# Sheet1.net
KiCad netlist of a schematic drawn in Altium Designer
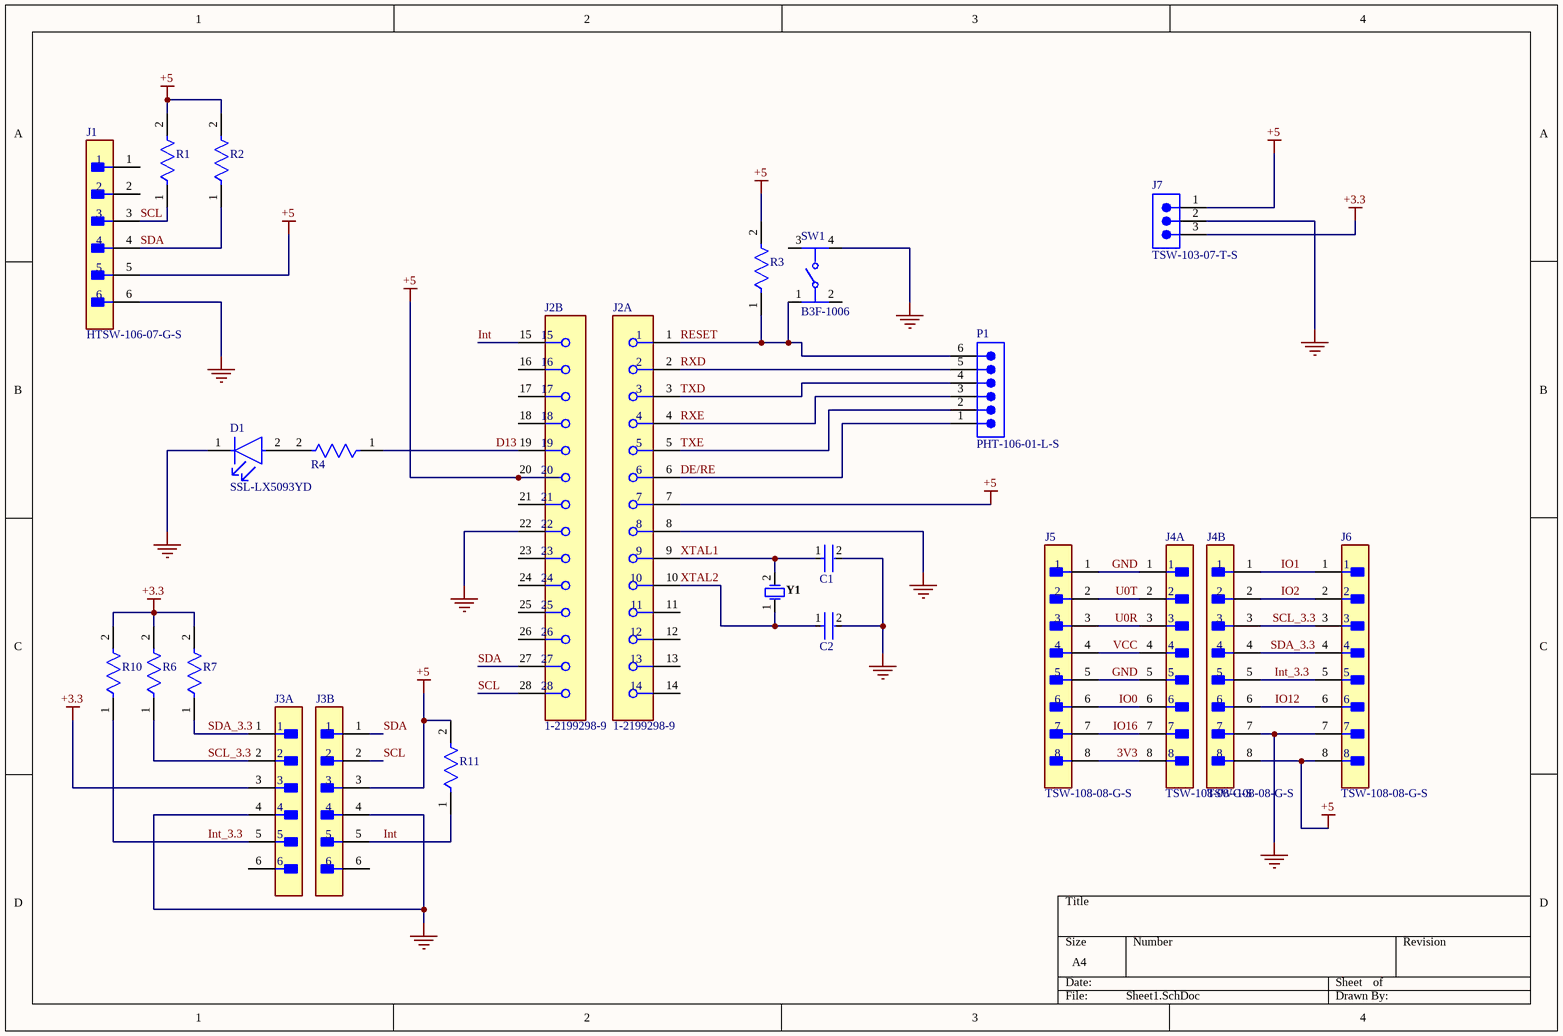
[diagram p0: Sheet1.SchDoc]

(export (version "E")
  (design (tool "Eeschema 10.0.6"))
  (components
    (comp (ref "C1")
      (value "RCE5C1H220J0DBH03A")
      (footprint "FP-RCE0DB-MFG")
      (description "Cap Ceramic 22pF 50V C0G ±5% Radial 2.5mm +125°C Ammo Pack")
      (fields (field (name "TOLERANCE") "5%"))
      (libsource (lib "Altium Content Vault") (part "b4654b650e69147ec39a6b967a45e02"))
    )
    (comp (ref "C2")
      (value "RCE5C1H220J0DBH03A")
      (footprint "FP-RCE0DB-MFG")
      (description "Cap Ceramic 22pF 50V C0G ±5% Radial 2.5mm +125°C Ammo Pack")
      (fields (field (name "TOLERANCE") "5%"))
      (libsource (lib "Altium Content Vault") (part "b4654b650e69147ec39a6b967a45e02"))
    )
    (comp (ref "D1")
      (value "SSL-LX5093YD")
      (footprint "FP-SSL-LX5093YD-MFG")
      (description "LED YELLOW DIFFUSED T-1 3/4 T/H")
      (libsource (lib "Altium Content Vault") (part "8706943c75ba83719d021d2fdc84c58"))
    )
    (comp (ref "J1")
      (value "HTSW-106-07-G-S")
      (footprint "FP-HTSW-106-07-G-S-MFG")
      (description "CONN HEADER VERT 6POS 2.54MM")
      (libsource (lib "Altium Content Vault") (part "f2cb566baf1c37ab5a3b8e90bbeafd6"))
    )
    (comp (ref "J2")
      (value "1-2199298-9")
      (footprint "FP-1-2199298-9-MFG")
      (description "CONN IC DIP SOCKET 28POS TIN")
      (libsource (lib "") (part "9ff29dcfa3a67afbf451aa7ba5e588e_1"))
    )
    (comp (ref "J3A")
      (value "TSW-106-22-G-S")
      (footprint "FP-TSW-106-22-G-S-MFG")
      (description "CONN HEADER VERT 6POS 2.54MM")
      (libsource (lib "") (part "11692be1245668b174829cb8722fdf5_1"))
    )
    (comp (ref "J3B")
      (value "TSW-106-22-G-S")
      (footprint "FP-TSW-106-22-G-S-MFG")
      (description "CONN HEADER VERT 6POS 2.54MM")
      (libsource (lib "Altium Content Vault") (part "11692be1245668b174829cb8722fdf5"))
    )
    (comp (ref "J4A")
      (value "TSW-108-08-G-S")
      (footprint "FP-TSW-108-08-G-S-MFG")
      (description "CONN HEADER VERT 8POS 2.54MM")
      (fields
        (field (name "MANUFACTURER") "Samtec")
        (field (name "OCTOPART") "https://octopart.com/tsw-108-08-g-s-samtec-272653")
      )
      (libsource (lib "") (part "99ec2b232beb5d2356d4d77f6a047f0_1"))
    )
    (comp (ref "J4B")
      (value "TSW-108-08-G-S")
      (footprint "FP-TSW-108-08-G-S-MFG")
      (description "CONN HEADER VERT 8POS 2.54MM")
      (fields
        (field (name "MANUFACTURER") "Samtec")
        (field (name "OCTOPART") "https://octopart.com/tsw-108-08-g-s-samtec-272653")
      )
      (libsource (lib "Altium Content Vault") (part "99ec2b232beb5d2356d4d77f6a047f0"))
    )
    (comp (ref "J5")
      (value "TSW-108-08-G-S")
      (footprint "FP-TSW-108-08-G-S-MFG")
      (description "CONN HEADER VERT 8POS 2.54MM")
      (fields
        (field (name "MANUFACTURER") "Samtec")
        (field (name "OCTOPART") "https://octopart.com/tsw-108-08-g-s-samtec-272653")
      )
      (libsource (lib "Altium Content Vault") (part "99ec2b232beb5d2356d4d77f6a047f0"))
    )
    (comp (ref "J6")
      (value "TSW-108-08-G-S")
      (footprint "FP-TSW-108-08-G-S-MFG")
      (description "CONN HEADER VERT 8POS 2.54MM")
      (fields
        (field (name "MANUFACTURER") "Samtec")
        (field (name "OCTOPART") "https://octopart.com/tsw-108-08-g-s-samtec-272653")
      )
      (libsource (lib "") (part "99ec2b232beb5d2356d4d77f6a047f0_1"))
    )
    (comp (ref "J7")
      (value "TSW-103-07-T-S")
      (footprint "SMTC-TSW-103-07-X-S")
      (description "0.025\" SQ Post Header, Through-hole, Vertical, -55 to 105 degC, 2.54 mm Pitch, 3-Pin, Male, RoHS")
      (fields (field (name "MANUFACTURER") "Samtec"))
      (libsource (lib "Altium Content Vault") (part "SMTC-TSW-103-X-X-S-X"))
    )
    (comp (ref "P1")
      (value "PHT-106-01-L-S")
      (footprint "SMTC-PHT-106-01-X-S")
      (description "Press Fit Header, Through-hole, Vertical, -55 to 125 degC, 2.54 mm Pitch, 6-Pin, Male, RoHS")
      (fields (field (name "MANUFACTURER") "Samtec"))
      (libsource (lib "Altium Content Vault") (part "SMTC-PHT-106-01-X-S"))
    )
    (comp (ref "R1")
      (value "VR37000001204JA100")
      (footprint "FP-VR37-MFG")
      (description "RES 1.2M OHM 5% 1/2W AXIAL")
      (fields (field (name "TOLERANCE") "5%"))
      (libsource (lib "Altium Content Vault") (part "1029c3af85768c4190bb7ad29bc67b5"))
    )
    (comp (ref "R2")
      (value "VR37000001204JA100")
      (footprint "FP-VR37-MFG")
      (description "RES 1.2M OHM 5% 1/2W AXIAL")
      (fields (field (name "TOLERANCE") "5%"))
      (libsource (lib "Altium Content Vault") (part "1029c3af85768c4190bb7ad29bc67b5"))
    )
    (comp (ref "R3")
      (value "VR37000001204JA100")
      (footprint "FP-VR37-MFG")
      (description "RES 1.2M OHM 5% 1/2W AXIAL")
      (fields (field (name "TOLERANCE") "5%"))
      (libsource (lib "Altium Content Vault") (part "1029c3af85768c4190bb7ad29bc67b5"))
    )
    (comp (ref "R4")
      (value "VR37000001204JA100")
      (footprint "FP-VR37-MFG")
      (description "RES 1.2M OHM 5% 1/2W AXIAL")
      (fields (field (name "TOLERANCE") "5%"))
      (libsource (lib "Altium Content Vault") (part "1029c3af85768c4190bb7ad29bc67b5"))
    )
    (comp (ref "R6")
      (value "VR37000001204JA100")
      (footprint "FP-VR37-MFG")
      (description "RES 1.2M OHM 5% 1/2W AXIAL")
      (fields (field (name "TOLERANCE") "5%"))
      (libsource (lib "Altium Content Vault") (part "1029c3af85768c4190bb7ad29bc67b5"))
    )
    (comp (ref "R7")
      (value "VR37000001204JA100")
      (footprint "FP-VR37-MFG")
      (description "RES 1.2M OHM 5% 1/2W AXIAL")
      (fields (field (name "TOLERANCE") "5%"))
      (libsource (lib "Altium Content Vault") (part "1029c3af85768c4190bb7ad29bc67b5"))
    )
    (comp (ref "R10")
      (value "VR37000001204JA100")
      (footprint "FP-VR37-MFG")
      (description "RES 1.2M OHM 5% 1/2W AXIAL")
      (fields (field (name "TOLERANCE") "5%"))
      (libsource (lib "Altium Content Vault") (part "1029c3af85768c4190bb7ad29bc67b5"))
    )
    (comp (ref "R11")
      (value "VR37000001204JA100")
      (footprint "FP-VR37-MFG")
      (description "RES 1.2M OHM 5% 1/2W AXIAL")
      (fields (field (name "TOLERANCE") "5%"))
      (libsource (lib "Altium Content Vault") (part "1029c3af85768c4190bb7ad29bc67b5"))
    )
    (comp (ref "SW1")
      (value "B3F-1006")
      (footprint "FP-B3F-1006-MFG")
      (description "SWITCH TACTILE SPST-NO 0.05A 24V")
      (libsource (lib "Altium Content Vault") (part "b8895f3f4cefb76e1819d2863dba89b"))
    )
    (comp (ref "Y1")
      (value "FOXSLF/160-20")
      (footprint "FOX-FOXSLF160-20")
      (description "Resistance Weld Thru-Hole Crystal, 16 MHz, -20 to 70 degC, 2-Pin THD, RoHS, Bulk")
      (fields (field (name "TOLERANCE") "1%"))
      (libsource (lib "Altium Content Vault") (part "XTAL-1-2-2"))
    )
  )
  (nets
    (net (code "1") (name "+3.3") (class "Default")
      (node (ref "J3A") (pin "3") (pinfunction "3_3") (pintype "passive"))
      (node (ref "J7") (pin "3") (pinfunction "3_3") (pintype "passive"))
      (node (ref "R10") (pin "2") (pinfunction "2_2") (pintype "passive"))
      (node (ref "R6") (pin "2") (pinfunction "2_2") (pintype "passive"))
      (node (ref "R7") (pin "2") (pinfunction "2_2") (pintype "passive"))
    )
    (net (code "2") (name "+5") (class "Default")
      (node (ref "J1") (pin "5") (pinfunction "5_5") (pintype "passive"))
      (node (ref "J2") (pin "20") (pinfunction "20_20") (pintype "passive"))
      (node (ref "J2") (pin "7") (pinfunction "7_7") (pintype "passive"))
      (node (ref "J3B") (pin "3") (pinfunction "3_3") (pintype "passive"))
      (node (ref "J4B") (pin "8") (pinfunction "8_8") (pintype "passive"))
      (node (ref "J6") (pin "8") (pinfunction "8_8") (pintype "passive"))
      (node (ref "J7") (pin "1") (pinfunction "1_1") (pintype "passive"))
      (node (ref "R1") (pin "2") (pinfunction "2_2") (pintype "passive"))
      (node (ref "R11") (pin "2") (pinfunction "2_2") (pintype "passive"))
      (node (ref "R2") (pin "2") (pinfunction "2_2") (pintype "passive"))
      (node (ref "R3") (pin "2") (pinfunction "2_2") (pintype "passive"))
    )
    (net (code "3") (name "/3V3") (class "Default")
      (node (ref "J4A") (pin "8") (pinfunction "8_8") (pintype "passive"))
      (node (ref "J5") (pin "8") (pinfunction "8_8") (pintype "passive"))
    )
    (net (code "4") (name "/D13") (class "Default")
      (node (ref "J2") (pin "19") (pinfunction "19_19") (pintype "passive"))
      (node (ref "R4") (pin "1") (pinfunction "1_1") (pintype "passive"))
    )
    (net (code "5") (name "/DE{slash}RE") (class "Default")
      (node (ref "J2") (pin "6") (pinfunction "6_6") (pintype "passive"))
      (node (ref "P1") (pin "1") (pinfunction "1_1") (pintype "passive"))
    )
    (net (code "6") (name "/IO0") (class "Default")
      (node (ref "J4A") (pin "6") (pinfunction "6_6") (pintype "passive"))
      (node (ref "J5") (pin "6") (pinfunction "6_6") (pintype "passive"))
    )
    (net (code "7") (name "/IO1") (class "Default")
      (node (ref "J4B") (pin "1") (pinfunction "1_1") (pintype "passive"))
      (node (ref "J6") (pin "1") (pinfunction "1_1") (pintype "passive"))
    )
    (net (code "8") (name "/IO2") (class "Default")
      (node (ref "J4B") (pin "2") (pinfunction "2_2") (pintype "passive"))
      (node (ref "J6") (pin "2") (pinfunction "2_2") (pintype "passive"))
    )
    (net (code "9") (name "/IO12") (class "Default")
      (node (ref "J4B") (pin "6") (pinfunction "6_6") (pintype "passive"))
      (node (ref "J6") (pin "6") (pinfunction "6_6") (pintype "passive"))
    )
    (net (code "10") (name "/IO16") (class "Default")
      (node (ref "J4A") (pin "7") (pinfunction "7_7") (pintype "passive"))
      (node (ref "J5") (pin "7") (pinfunction "7_7") (pintype "passive"))
    )
    (net (code "11") (name "/Int") (class "Default")
      (node (ref "J2") (pin "15") (pinfunction "15_15") (pintype "passive"))
      (node (ref "J3B") (pin "5") (pinfunction "5_5") (pintype "passive"))
      (node (ref "R11") (pin "1") (pinfunction "1_1") (pintype "passive"))
    )
    (net (code "12") (name "/Int_3.3") (class "Default")
      (node (ref "J3A") (pin "5") (pinfunction "5_5") (pintype "passive"))
      (node (ref "J4B") (pin "5") (pinfunction "5_5") (pintype "passive"))
      (node (ref "J6") (pin "5") (pinfunction "5_5") (pintype "passive"))
      (node (ref "R10") (pin "1") (pinfunction "1_1") (pintype "passive"))
    )
    (net (code "13") (name "/RESET") (class "Default")
      (node (ref "J2") (pin "1") (pinfunction "1_1") (pintype "passive"))
      (node (ref "P1") (pin "6") (pinfunction "6_6") (pintype "passive"))
      (node (ref "R3") (pin "1") (pinfunction "1_1") (pintype "passive"))
      (node (ref "SW1") (pin "1") (pinfunction "1_1") (pintype "passive"))
    )
    (net (code "14") (name "/RXD") (class "Default")
      (node (ref "J2") (pin "2") (pinfunction "2_2") (pintype "passive"))
      (node (ref "P1") (pin "5") (pinfunction "5_5") (pintype "passive"))
    )
    (net (code "15") (name "/RXE") (class "Default")
      (node (ref "J2") (pin "4") (pinfunction "4_4") (pintype "passive"))
      (node (ref "P1") (pin "3") (pinfunction "3_3") (pintype "passive"))
    )
    (net (code "16") (name "/SCL") (class "Default")
      (node (ref "J1") (pin "3") (pinfunction "3_3") (pintype "passive"))
      (node (ref "J2") (pin "28") (pinfunction "28_28") (pintype "passive"))
      (node (ref "J3B") (pin "2") (pinfunction "2_2") (pintype "passive"))
      (node (ref "R1") (pin "1") (pinfunction "1_1") (pintype "passive"))
    )
    (net (code "17") (name "/SCL_3.3") (class "Default")
      (node (ref "J3A") (pin "2") (pinfunction "2_2") (pintype "passive"))
      (node (ref "J4B") (pin "3") (pinfunction "3_3") (pintype "passive"))
      (node (ref "J6") (pin "3") (pinfunction "3_3") (pintype "passive"))
      (node (ref "R6") (pin "1") (pinfunction "1_1") (pintype "passive"))
    )
    (net (code "18") (name "/SDA") (class "Default")
      (node (ref "J1") (pin "4") (pinfunction "4_4") (pintype "passive"))
      (node (ref "J2") (pin "27") (pinfunction "27_27") (pintype "passive"))
      (node (ref "J3B") (pin "1") (pinfunction "1_1") (pintype "passive"))
      (node (ref "R2") (pin "1") (pinfunction "1_1") (pintype "passive"))
    )
    (net (code "19") (name "/SDA_3.3") (class "Default")
      (node (ref "J3A") (pin "1") (pinfunction "1_1") (pintype "passive"))
      (node (ref "J4B") (pin "4") (pinfunction "4_4") (pintype "passive"))
      (node (ref "J6") (pin "4") (pinfunction "4_4") (pintype "passive"))
      (node (ref "R7") (pin "1") (pinfunction "1_1") (pintype "passive"))
    )
    (net (code "20") (name "/TXD") (class "Default")
      (node (ref "J2") (pin "3") (pinfunction "3_3") (pintype "passive"))
      (node (ref "P1") (pin "4") (pinfunction "4_4") (pintype "passive"))
    )
    (net (code "21") (name "/TXE") (class "Default")
      (node (ref "J2") (pin "5") (pinfunction "5_5") (pintype "passive"))
      (node (ref "P1") (pin "2") (pinfunction "2_2") (pintype "passive"))
    )
    (net (code "22") (name "/U0R") (class "Default")
      (node (ref "J4A") (pin "3") (pinfunction "3_3") (pintype "passive"))
      (node (ref "J5") (pin "3") (pinfunction "3_3") (pintype "passive"))
    )
    (net (code "23") (name "/U0T") (class "Default")
      (node (ref "J4A") (pin "2") (pinfunction "2_2") (pintype "passive"))
      (node (ref "J5") (pin "2") (pinfunction "2_2") (pintype "passive"))
    )
    (net (code "24") (name "/VCC") (class "Default")
      (node (ref "J4A") (pin "4") (pinfunction "4_4") (pintype "passive"))
      (node (ref "J5") (pin "4") (pinfunction "4_4") (pintype "passive"))
    )
    (net (code "25") (name "/XTAL1") (class "Default")
      (node (ref "C1") (pin "1") (pinfunction "1_1") (pintype "passive"))
      (node (ref "J2") (pin "9") (pinfunction "9_9") (pintype "passive"))
      (node (ref "Y1") (pin "2") (pinfunction "2_2") (pintype "passive"))
    )
    (net (code "26") (name "/XTAL2") (class "Default")
      (node (ref "C2") (pin "1") (pinfunction "1_1") (pintype "passive"))
      (node (ref "J2") (pin "10") (pinfunction "10_10") (pintype "passive"))
      (node (ref "Y1") (pin "1") (pinfunction "1_1") (pintype "passive"))
    )
    (net (code "27") (name "GND") (class "Default")
      (node (ref "C1") (pin "2") (pinfunction "2_2") (pintype "passive"))
      (node (ref "C2") (pin "2") (pinfunction "2_2") (pintype "passive"))
      (node (ref "D1") (pin "1") (pinfunction "C_1") (pintype "passive"))
      (node (ref "J1") (pin "6") (pinfunction "6_6") (pintype "passive"))
      (node (ref "J2") (pin "22") (pinfunction "22_22") (pintype "passive"))
      (node (ref "J2") (pin "8") (pinfunction "8_8") (pintype "passive"))
      (node (ref "J3A") (pin "4") (pinfunction "4_4") (pintype "passive"))
      (node (ref "J3B") (pin "4") (pinfunction "4_4") (pintype "passive"))
      (node (ref "J4A") (pin "1") (pinfunction "1_1") (pintype "passive"))
      (node (ref "J4A") (pin "5") (pinfunction "5_5") (pintype "passive"))
      (node (ref "J4B") (pin "7") (pinfunction "7_7") (pintype "passive"))
      (node (ref "J5") (pin "1") (pinfunction "1_1") (pintype "passive"))
      (node (ref "J5") (pin "5") (pinfunction "5_5") (pintype "passive"))
      (node (ref "J6") (pin "7") (pinfunction "7_7") (pintype "passive"))
      (node (ref "J7") (pin "2") (pinfunction "2_2") (pintype "passive"))
      (node (ref "SW1") (pin "4") (pinfunction "4_4") (pintype "passive"))
    )
    (net (code "28") (name "Net-(D1-A)") (class "Default")
      (node (ref "D1") (pin "2") (pinfunction "A_2") (pintype "passive"))
      (node (ref "R4") (pin "2") (pinfunction "2_2") (pintype "passive"))
    )
    (net (code "29") (name "unconnected-(J1-Pad1)") (class "Default")
      (node (ref "J1") (pin "1") (pinfunction "1_1") (pintype "passive"))
    )
    (net (code "30") (name "unconnected-(J1-Pad2)") (class "Default")
      (node (ref "J1") (pin "2") (pinfunction "2_2") (pintype "passive"))
    )
    (net (code "31") (name "unconnected-(J2-Pad11)") (class "Default")
      (node (ref "J2") (pin "11") (pinfunction "11_11") (pintype "passive"))
    )
    (net (code "32") (name "unconnected-(J2-Pad12)") (class "Default")
      (node (ref "J2") (pin "12") (pinfunction "12_12") (pintype "passive"))
    )
    (net (code "33") (name "unconnected-(J2-Pad13)") (class "Default")
      (node (ref "J2") (pin "13") (pinfunction "13_13") (pintype "passive"))
    )
    (net (code "34") (name "unconnected-(J2-Pad14)") (class "Default")
      (node (ref "J2") (pin "14") (pinfunction "14_14") (pintype "passive"))
    )
    (net (code "35") (name "unconnected-(J2-Pad16)") (class "Default")
      (node (ref "J2") (pin "16") (pinfunction "16_16") (pintype "passive"))
    )
    (net (code "36") (name "unconnected-(J2-Pad17)") (class "Default")
      (node (ref "J2") (pin "17") (pinfunction "17_17") (pintype "passive"))
    )
    (net (code "37") (name "unconnected-(J2-Pad18)") (class "Default")
      (node (ref "J2") (pin "18") (pinfunction "18_18") (pintype "passive"))
    )
    (net (code "38") (name "unconnected-(J2-Pad21)") (class "Default")
      (node (ref "J2") (pin "21") (pinfunction "21_21") (pintype "passive"))
    )
    (net (code "39") (name "unconnected-(J2-Pad23)") (class "Default")
      (node (ref "J2") (pin "23") (pinfunction "23_23") (pintype "passive"))
    )
    (net (code "40") (name "unconnected-(J2-Pad24)") (class "Default")
      (node (ref "J2") (pin "24") (pinfunction "24_24") (pintype "passive"))
    )
    (net (code "41") (name "unconnected-(J2-Pad25)") (class "Default")
      (node (ref "J2") (pin "25") (pinfunction "25_25") (pintype "passive"))
    )
    (net (code "42") (name "unconnected-(J2-Pad26)") (class "Default")
      (node (ref "J2") (pin "26") (pinfunction "26_26") (pintype "passive"))
    )
    (net (code "43") (name "unconnected-(J3A-Pad6)") (class "Default")
      (node (ref "J3A") (pin "6") (pinfunction "6_6") (pintype "passive"))
    )
    (net (code "44") (name "unconnected-(J3B-Pad6)") (class "Default")
      (node (ref "J3B") (pin "6") (pinfunction "6_6") (pintype "passive"))
    )
    (net (code "45") (name "unconnected-(SW1-Pad2)") (class "Default")
      (node (ref "SW1") (pin "2") (pinfunction "2_2") (pintype "passive"))
    )
    (net (code "46") (name "unconnected-(SW1-Pad3)") (class "Default")
      (node (ref "SW1") (pin "3") (pinfunction "3_3") (pintype "passive"))
    )
  )
)
